# BSPD_V1_1.net
KiCad netlist of a schematic drawn in Altium Designer
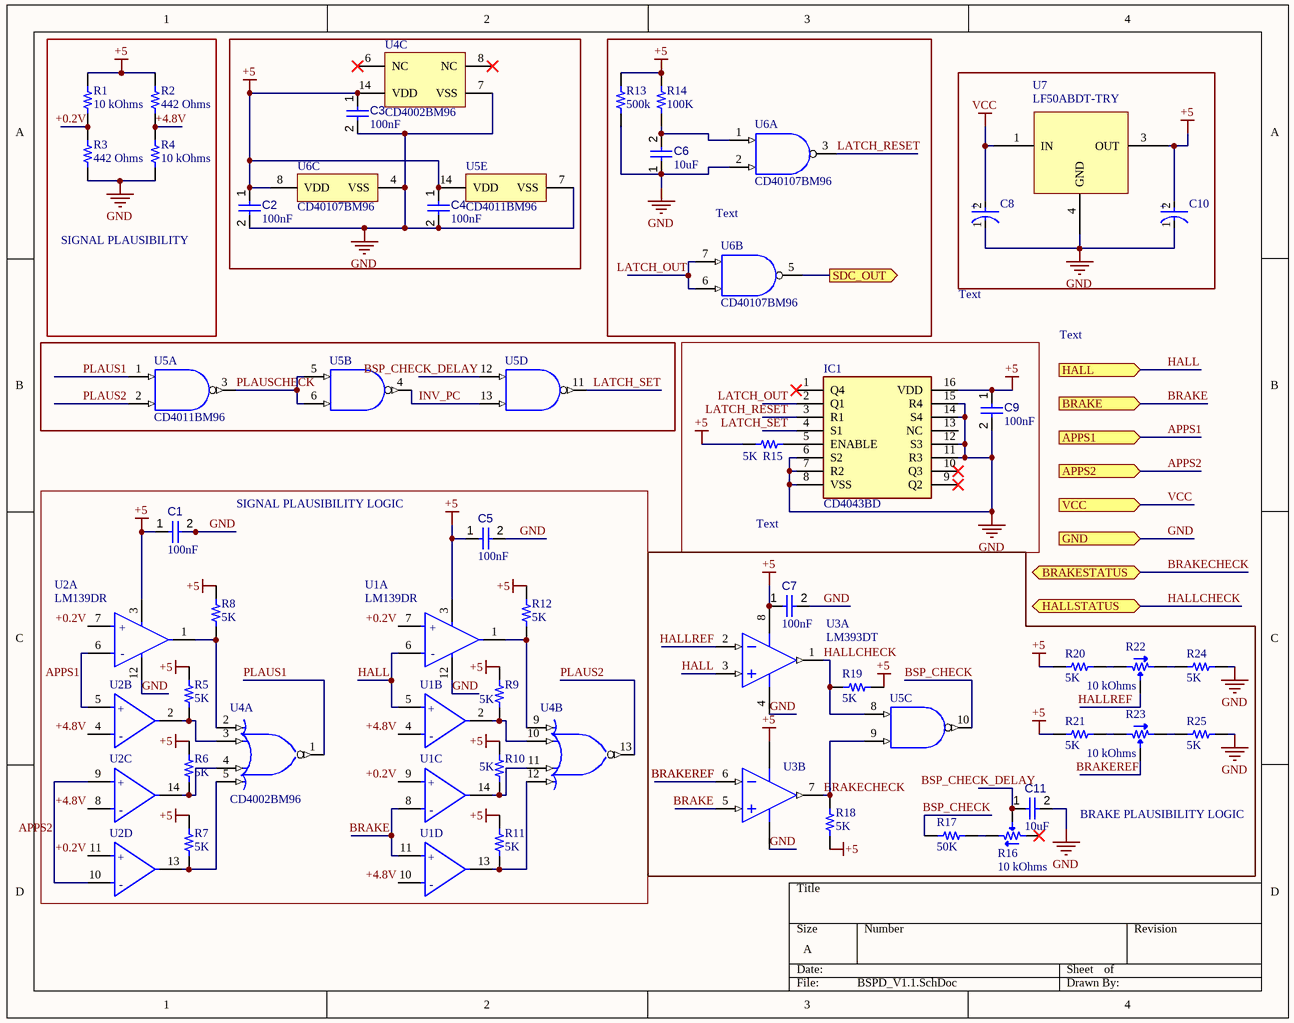
[diagram p0: BSPD_V1.1.SchDoc]

(export (version "E")
  (design (tool "Eeschema 10.0.6"))
  (components
    (comp (ref "C1")
      (value "100nF")
      (footprint "CAPC1608X90X40NL10T20")
      (description "Chip Capacitor, 100 nF, +/- 10%, 50 V, 0603 (1608 Metric)")
      (fields (field (name "TOLERANCE") "10%") (field (name "Comment") "Capacitor 100 nF +/-10% 50 V 0603"))
      (libsource (lib "Kennesaw Motorsports") (part "CAP-NP-2"))
    )
    (comp (ref "C2")
      (value "100nF")
      (footprint "CAPC1608X90X40NL10T20")
      (description "Chip Capacitor, 100 nF, +/- 10%, 50 V, 0603 (1608 Metric)")
      (fields (field (name "TOLERANCE") "10%") (field (name "Comment") "Capacitor 100 nF +/-10% 50 V 0603"))
      (libsource (lib "Kennesaw Motorsports") (part "CAP-NP-2"))
    )
    (comp (ref "C3")
      (value "100nF")
      (footprint "CAPC1608X90X40NL10T20")
      (description "Chip Capacitor, 100 nF, +/- 10%, 50 V, 0603 (1608 Metric)")
      (fields (field (name "TOLERANCE") "10%") (field (name "Comment") "Capacitor 100 nF +/-10% 50 V 0603"))
      (libsource (lib "Kennesaw Motorsports") (part "CAP-NP-2"))
    )
    (comp (ref "C4")
      (value "100nF")
      (footprint "CAPC1608X90X40NL10T20")
      (description "Chip Capacitor, 100 nF, +/- 10%, 50 V, 0603 (1608 Metric)")
      (fields (field (name "TOLERANCE") "10%") (field (name "Comment") "Capacitor 100 nF +/-10% 50 V 0603"))
      (libsource (lib "Kennesaw Motorsports") (part "CAP-NP-2"))
    )
    (comp (ref "C5")
      (value "100nF")
      (footprint "CAPC1608X90X40NL10T20")
      (description "Chip Capacitor, 100 nF, +/- 10%, 50 V, 0603 (1608 Metric)")
      (fields (field (name "TOLERANCE") "10%") (field (name "Comment") "Capacitor 100 nF +/-10% 50 V 0603"))
      (libsource (lib "Kennesaw Motorsports") (part "CAP-NP-2"))
    )
    (comp (ref "C6")
      (value "10uF")
      (footprint "CAPC1608X90X40NL10T20")
      (description "Chip Capacitor, 100 nF, +/- 10%, 50 V, 0603 (1608 Metric)")
      (fields (field (name "TOLERANCE") "10%") (field (name "Comment") "Capacitor 100 nF +/-10% 50 V 0603"))
      (libsource (lib "Kennesaw Motorsports") (part "CAP-NP-2"))
    )
    (comp (ref "C7")
      (value "100nF")
      (footprint "CAPC1608X90X40NL10T20")
      (description "Chip Capacitor, 100 nF, +/- 10%, 50 V, 0603 (1608 Metric)")
      (fields (field (name "TOLERANCE") "10%") (field (name "Comment") "Capacitor 100 nF +/-10% 50 V 0603"))
      (libsource (lib "Kennesaw Motorsports") (part "CAP-NP-2"))
    )
    (comp (ref "C8")
      (value "EEEFK1E100R")
      (footprint "FP-FKB-MFG")
      (description "CAP ALUM 10UF 20% 25V SMD")
      (fields (field (name "VOLTAGE") "25V") (field (name "TOLERANCE") "20%"))
      (libsource (lib "Altium Content Vault") (part "203bc49f2ac43e59fd269a8c329ed05"))
    )
    (comp (ref "C9")
      (value "100nF")
      (footprint "CAPC1608X90X40NL10T20")
      (description "Chip Capacitor, 100 nF, +/- 10%, 50 V, 0603 (1608 Metric)")
      (fields (field (name "TOLERANCE") "10%") (field (name "Comment") "Capacitor 100 nF +/-10% 50 V 0603"))
      (libsource (lib "Kennesaw Motorsports") (part "CAP-NP-2"))
    )
    (comp (ref "C10")
      (value "EEEFK1E100R")
      (footprint "FP-FKB-MFG")
      (description "CAP ALUM 10UF 20% 25V SMD")
      (fields (field (name "VOLTAGE") "25V") (field (name "TOLERANCE") "20%"))
      (libsource (lib "Altium Content Vault") (part "203bc49f2ac43e59fd269a8c329ed05"))
    )
    (comp (ref "C11")
      (value "10uF")
      (footprint "CAPC1608X90X40NL10T20")
      (description "Chip Capacitor, 100 nF, +/- 10%, 50 V, 0603 (1608 Metric)")
      (fields (field (name "TOLERANCE") "10%") (field (name "Comment") "Capacitor 100 nF +/-10% 50 V 0603"))
      (libsource (lib "Kennesaw Motorsports") (part "CAP-NP-2"))
    )
    (comp (ref "IC1")
      (value "CD4043BD")
      (footprint "SamacSys:SOIC127P600X175-16N")
      (description "Integrated Circuit")
      (fields (field (name "MOUSER PART NUMBER") "595-CD4043BD"))
      (libsource (lib "*") (part "CD4043BD"))
    )
    (comp (ref "R1")
      (value "10 kOhms")
      (footprint "RES 0603_1608")
      (description "RES SMD 10K OHM 0.1% 1/16W 0603")
      (fields
        (field (name "PART NUMBER") "CPF0603B10KE")
        (field (name "MANUFACTURER") "TE Connectivity Passive Product")
      )
      (libsource (lib "Celestial Altium Library - altium_library") (part "Resistor"))
    )
    (comp (ref "R2")
      (value "442 Ohms")
      (footprint "RES 0603_1608")
      (description "RES 442 OHM 1% 1/8W 0603")
      (fields
        (field (name "PART NUMBER") "RK73H1JTTD4420F")
        (field (name "MANUFACTURER") "KOA Speer Electronics, Inc.")
      )
      (libsource (lib "Celestial Altium Library - altium_library") (part "Resistor"))
    )
    (comp (ref "R3")
      (value "442 Ohms")
      (footprint "RES 0603_1608")
      (description "RES 442 OHM 1% 1/8W 0603")
      (fields
        (field (name "PART NUMBER") "RK73H1JTTD4420F")
        (field (name "MANUFACTURER") "KOA Speer Electronics, Inc.")
      )
      (libsource (lib "Celestial Altium Library - altium_library") (part "Resistor"))
    )
    (comp (ref "R4")
      (value "10 kOhms")
      (footprint "RES 0603_1608")
      (description "RES SMD 10K OHM 0.1% 1/16W 0603")
      (fields
        (field (name "PART NUMBER") "CPF0603B10KE")
        (field (name "MANUFACTURER") "TE Connectivity Passive Product")
      )
      (libsource (lib "Celestial Altium Library - altium_library") (part "Resistor"))
    )
    (comp (ref "R5")
      (value "5K")
      (footprint "RES 0603_1608")
      (description "CRGP 0603 5K6 1%")
      (fields
        (field (name "PART NUMBER") "CRGP0603F5K6")
        (field (name "MANUFACTURER") "TE Connectivity Passive Product")
      )
      (libsource (lib "Celestial Altium Library - altium_library") (part "Resistor"))
    )
    (comp (ref "R6")
      (value "5K")
      (footprint "RES 0603_1608")
      (description "CRGP 0603 5K6 1%")
      (fields
        (field (name "PART NUMBER") "CRGP0603F5K6")
        (field (name "MANUFACTURER") "TE Connectivity Passive Product")
      )
      (libsource (lib "Celestial Altium Library - altium_library") (part "Resistor"))
    )
    (comp (ref "R7")
      (value "5K")
      (footprint "RES 0603_1608")
      (description "CRGP 0603 5K6 1%")
      (fields
        (field (name "PART NUMBER") "CRGP0603F5K6")
        (field (name "MANUFACTURER") "TE Connectivity Passive Product")
      )
      (libsource (lib "Celestial Altium Library - altium_library") (part "Resistor"))
    )
    (comp (ref "R8")
      (value "5K")
      (footprint "RES 0603_1608")
      (description "CRGP 0603 5K6 1%")
      (fields
        (field (name "PART NUMBER") "CRGP0603F5K6")
        (field (name "MANUFACTURER") "TE Connectivity Passive Product")
      )
      (libsource (lib "Celestial Altium Library - altium_library") (part "Resistor"))
    )
    (comp (ref "R9")
      (value "5K")
      (footprint "RES 0603_1608")
      (description "CRGP 0603 5K6 1%")
      (fields
        (field (name "PART NUMBER") "CRGP0603F5K6")
        (field (name "MANUFACTURER") "TE Connectivity Passive Product")
      )
      (libsource (lib "Celestial Altium Library - altium_library") (part "Resistor"))
    )
    (comp (ref "R10")
      (value "5K")
      (footprint "RES 0603_1608")
      (description "CRGP 0603 5K6 1%")
      (fields
        (field (name "PART NUMBER") "CRGP0603F5K6")
        (field (name "MANUFACTURER") "TE Connectivity Passive Product")
      )
      (libsource (lib "Celestial Altium Library - altium_library") (part "Resistor"))
    )
    (comp (ref "R11")
      (value "5K")
      (footprint "RES 0603_1608")
      (description "CRGP 0603 5K6 1%")
      (fields
        (field (name "PART NUMBER") "CRGP0603F5K6")
        (field (name "MANUFACTURER") "TE Connectivity Passive Product")
      )
      (libsource (lib "Celestial Altium Library - altium_library") (part "Resistor"))
    )
    (comp (ref "R12")
      (value "5K")
      (footprint "RES 0603_1608")
      (description "CRGP 0603 5K6 1%")
      (fields
        (field (name "PART NUMBER") "CRGP0603F5K6")
        (field (name "MANUFACTURER") "TE Connectivity Passive Product")
      )
      (libsource (lib "Celestial Altium Library - altium_library") (part "Resistor"))
    )
    (comp (ref "R13")
      (value "500k")
      (footprint "RES 0603_1608")
      (description "CRGP 0603 5K6 1%")
      (fields
        (field (name "PART NUMBER") "CRGP0603F5K6")
        (field (name "MANUFACTURER") "TE Connectivity Passive Product")
      )
      (libsource (lib "Celestial Altium Library - altium_library") (part "Resistor"))
    )
    (comp (ref "R14")
      (value "100K")
      (footprint "RES 0603_1608")
      (description "CRGP 0603 5K6 1%")
      (fields
        (field (name "PART NUMBER") "CRGP0603F5K6")
        (field (name "MANUFACTURER") "TE Connectivity Passive Product")
      )
      (libsource (lib "Celestial Altium Library - altium_library") (part "Resistor"))
    )
    (comp (ref "R15")
      (value "5K")
      (footprint "RES 0603_1608")
      (description "CRGP 0603 5K6 1%")
      (fields
        (field (name "PART NUMBER") "CRGP0603F5K6")
        (field (name "MANUFACTURER") "TE Connectivity Passive Product")
      )
      (libsource (lib "Celestial Altium Library - altium_library") (part "Resistor"))
    )
    (comp (ref "R16")
      (value "10 kOhms")
      (footprint "POT BOURNS TRIMPOT TC33")
      (description "TRIMMER 10K OHM 0.1W J LEAD TOP")
      (fields (field (name "PART NUMBER") "TC33X-2-103E") (field (name "MANUFACTURER") "Bourns Inc."))
      (libsource (lib "Celestial Altium Library - altium_library") (part "Potentiometer"))
    )
    (comp (ref "R17")
      (value "50K")
      (footprint "RES 0603_1608")
      (description "CRGP 0603 5K6 1%")
      (fields
        (field (name "PART NUMBER") "CRGP0603F5K6")
        (field (name "MANUFACTURER") "TE Connectivity Passive Product")
      )
      (libsource (lib "Celestial Altium Library - altium_library") (part "Resistor"))
    )
    (comp (ref "R18")
      (value "5K")
      (footprint "RES 0603_1608")
      (description "CRGP 0603 5K6 1%")
      (fields
        (field (name "PART NUMBER") "CRGP0603F5K6")
        (field (name "MANUFACTURER") "TE Connectivity Passive Product")
      )
      (libsource (lib "Celestial Altium Library - altium_library") (part "Resistor"))
    )
    (comp (ref "R19")
      (value "5K")
      (footprint "RES 0603_1608")
      (description "CRGP 0603 5K6 1%")
      (fields
        (field (name "PART NUMBER") "CRGP0603F5K6")
        (field (name "MANUFACTURER") "TE Connectivity Passive Product")
      )
      (libsource (lib "Celestial Altium Library - altium_library") (part "Resistor"))
    )
    (comp (ref "R20")
      (value "5K")
      (footprint "RES 0603_1608")
      (description "CRGP 0603 5K6 1%")
      (fields
        (field (name "PART NUMBER") "CRGP0603F5K6")
        (field (name "MANUFACTURER") "TE Connectivity Passive Product")
      )
      (libsource (lib "Celestial Altium Library - altium_library") (part "Resistor"))
    )
    (comp (ref "R21")
      (value "5K")
      (footprint "RES 0603_1608")
      (description "CRGP 0603 5K6 1%")
      (fields
        (field (name "PART NUMBER") "CRGP0603F5K6")
        (field (name "MANUFACTURER") "TE Connectivity Passive Product")
      )
      (libsource (lib "Celestial Altium Library - altium_library") (part "Resistor"))
    )
    (comp (ref "R22")
      (value "10 kOhms")
      (footprint "POT BOURNS TRIMPOT TC33")
      (description "TRIMMER 10K OHM 0.1W J LEAD TOP")
      (fields (field (name "PART NUMBER") "TC33X-2-103E") (field (name "MANUFACTURER") "Bourns Inc."))
      (libsource (lib "Celestial Altium Library - altium_library") (part "Potentiometer"))
    )
    (comp (ref "R23")
      (value "10 kOhms")
      (footprint "POT BOURNS TRIMPOT TC33")
      (description "TRIMMER 10K OHM 0.1W J LEAD TOP")
      (fields (field (name "PART NUMBER") "TC33X-2-103E") (field (name "MANUFACTURER") "Bourns Inc."))
      (libsource (lib "Celestial Altium Library - altium_library") (part "Potentiometer"))
    )
    (comp (ref "R24")
      (value "5K")
      (footprint "RES 0603_1608")
      (description "CRGP 0603 5K6 1%")
      (fields
        (field (name "PART NUMBER") "CRGP0603F5K6")
        (field (name "MANUFACTURER") "TE Connectivity Passive Product")
      )
      (libsource (lib "Celestial Altium Library - altium_library") (part "Resistor"))
    )
    (comp (ref "R25")
      (value "5K")
      (footprint "RES 0603_1608")
      (description "CRGP 0603 5K6 1%")
      (fields
        (field (name "PART NUMBER") "CRGP0603F5K6")
        (field (name "MANUFACTURER") "TE Connectivity Passive Product")
      )
      (libsource (lib "Celestial Altium Library - altium_library") (part "Resistor"))
    )
    (comp (ref "U1")
      (value "LM139DR")
      (footprint "FP-D0014A-IPC_C")
      (description "IC QUAD DIFF COMPARATOR 14-SOIC")
      (libsource (lib "Altium Content Vault") (part "194f83ff06066585c623a61d885a339"))
    )
    (comp (ref "U2")
      (value "LM139DR")
      (footprint "FP-D0014A-IPC_C")
      (description "IC QUAD DIFF COMPARATOR 14-SOIC")
      (libsource (lib "Altium Content Vault") (part "194f83ff06066585c623a61d885a339"))
    )
    (comp (ref "U3")
      (value "LM393DT")
      (footprint "STM-SO-8_D_L")
      (description "Low-Power, Dual-Voltage Comparator, 2 to 36 V, 0 to 70 degC, 8-Pin SOIC (SO), RoHS, Tape and Reel")
      (fields (field (name "MANUFACTURER") "STMicroelectronics"))
      (libsource (lib "Altium Content Vault") (part "STM-LM393-SO8"))
    )
    (comp (ref "U4")
      (value "CD4002BM96")
      (footprint "D0014A_L")
      (description "CMOS Dual 4-Input NOR Gate, D0014A, LARGE T&R")
      (fields
        (field (name "MANUFACTURER") "Texas Instruments")
        (field (name "GENERIC PART NUMBER") "CD4002B")
      )
      (libsource (lib "Altium Content Vault") (part "TI-CD4002B-D0014A-14"))
    )
    (comp (ref "U5")
      (value "CD4011BM96")
      (footprint "D0014A_L")
      (description "CMOS Quad 2-Input NAND Gate, D0014A, LARGE T&R")
      (fields
        (field (name "MANUFACTURER") "Texas Instruments")
        (field (name "GENERIC PART NUMBER") "CD4011B")
      )
      (libsource (lib "Altium Content Vault") (part "TI-NAND-4-2IN-14_A"))
    )
    (comp (ref "U6")
      (value "CD40107BM96")
      (footprint "D0008A_N")
      (description "CMOS Dual 2-Input NAND Buffer/Driver, D0008A, LARGE T&R")
      (fields
        (field (name "MANUFACTURER") "Texas Instruments")
        (field (name "GENERIC PART NUMBER") "CD40107B")
      )
      (libsource (lib "Altium Content Vault") (part "TI-CD40107B-8"))
    )
    (comp (ref "U7")
      (value "LF50ABDT-TRY")
      (footprint "DPAK228P972X238-3N")
      (description "Linear Voltage Regulator IC Positive Fixed 1 Output 500mA DPAK")
      (libsource (lib "LF50ABDT-TRY") (part "LF50ABDT-TRY"))
    )
  )
  (nets
    (net (code "1") (name "+5") (class "Default")
      (node (ref "C1") (pin "1") (pinfunction "1_1") (pintype "passive"))
      (node (ref "C10") (pin "2") (pinfunction "A_2") (pintype "passive"))
      (node (ref "C2") (pin "1") (pinfunction "1_1") (pintype "passive"))
      (node (ref "C3") (pin "1") (pinfunction "1_1") (pintype "passive"))
      (node (ref "C4") (pin "1") (pinfunction "1_1") (pintype "passive"))
      (node (ref "C5") (pin "1") (pinfunction "1_1") (pintype "passive"))
      (node (ref "C7") (pin "1") (pinfunction "1_1") (pintype "passive"))
      (node (ref "C9") (pin "1") (pinfunction "1_1") (pintype "passive"))
      (node (ref "IC1") (pin "16") (pinfunction "VDD_16") (pintype "passive"))
      (node (ref "R1") (pin "2") (pinfunction "2_2") (pintype "passive"))
      (node (ref "R10") (pin "1") (pinfunction "1_1") (pintype "passive"))
      (node (ref "R11") (pin "1") (pinfunction "1_1") (pintype "passive"))
      (node (ref "R12") (pin "1") (pinfunction "1_1") (pintype "passive"))
      (node (ref "R13") (pin "2") (pinfunction "2_2") (pintype "passive"))
      (node (ref "R14") (pin "2") (pinfunction "2_2") (pintype "passive"))
      (node (ref "R15") (pin "2") (pinfunction "2_2") (pintype "passive"))
      (node (ref "R18") (pin "1") (pinfunction "1_1") (pintype "passive"))
      (node (ref "R19") (pin "1") (pinfunction "1_1") (pintype "passive"))
      (node (ref "R2") (pin "1") (pinfunction "1_1") (pintype "passive"))
      (node (ref "R20") (pin "1") (pinfunction "1_1") (pintype "passive"))
      (node (ref "R21") (pin "1") (pinfunction "1_1") (pintype "passive"))
      (node (ref "R5") (pin "1") (pinfunction "1_1") (pintype "passive"))
      (node (ref "R6") (pin "1") (pinfunction "1_1") (pintype "passive"))
      (node (ref "R7") (pin "1") (pinfunction "1_1") (pintype "passive"))
      (node (ref "R8") (pin "1") (pinfunction "1_1") (pintype "passive"))
      (node (ref "R9") (pin "1") (pinfunction "1_1") (pintype "passive"))
      (node (ref "U1") (pin "3") (pinfunction "VCC_3") (pintype "power_in"))
      (node (ref "U2") (pin "3") (pinfunction "VCC_3") (pintype "power_in"))
      (node (ref "U3") (pin "8") (pinfunction "VCC+_8") (pintype "power_in"))
      (node (ref "U4") (pin "14") (pinfunction "VDD_14") (pintype "power_in"))
      (node (ref "U5") (pin "14") (pinfunction "VDD_14") (pintype "power_in"))
      (node (ref "U6") (pin "8") (pinfunction "VDD_8") (pintype "power_in"))
      (node (ref "U7") (pin "3") (pinfunction "OUT_3") (pintype "power_in"))
    )
    (net (code "2") (name "/+0.2V") (class "Default")
      (node (ref "R1") (pin "1") (pinfunction "1_1") (pintype "passive"))
      (node (ref "R3") (pin "2") (pinfunction "2_2") (pintype "passive"))
      (node (ref "U1") (pin "7") (pinfunction "1IN+_7") (pintype "tri_state"))
      (node (ref "U1") (pin "9") (pinfunction "3IN+_9") (pintype "tri_state"))
      (node (ref "U2") (pin "11") (pinfunction "4IN+_11") (pintype "tri_state"))
      (node (ref "U2") (pin "7") (pinfunction "1IN+_7") (pintype "tri_state"))
    )
    (net (code "3") (name "/+4.8V") (class "Default")
      (node (ref "R2") (pin "2") (pinfunction "2_2") (pintype "passive"))
      (node (ref "R4") (pin "2") (pinfunction "2_2") (pintype "passive"))
      (node (ref "U1") (pin "10") (pinfunction "4IN-_10") (pintype "tri_state"))
      (node (ref "U1") (pin "4") (pinfunction "2IN-_4") (pintype "tri_state"))
      (node (ref "U2") (pin "4") (pinfunction "2IN-_4") (pintype "tri_state"))
      (node (ref "U2") (pin "8") (pinfunction "3IN-_8") (pintype "tri_state"))
    )
    (net (code "4") (name "/APPS1") (class "Default")
      (node (ref "U2") (pin "5") (pinfunction "2IN+_5") (pintype "tri_state"))
      (node (ref "U2") (pin "6") (pinfunction "1IN-_6") (pintype "tri_state"))
    )
    (net (code "5") (name "/APPS2") (class "Default")
      (node (ref "U2") (pin "10") (pinfunction "4IN-_10") (pintype "tri_state"))
      (node (ref "U2") (pin "9") (pinfunction "3IN+_9") (pintype "tri_state"))
    )
    (net (code "6") (name "/BRAKE") (class "Default")
      (node (ref "U1") (pin "11") (pinfunction "4IN+_11") (pintype "tri_state"))
      (node (ref "U1") (pin "8") (pinfunction "3IN-_8") (pintype "tri_state"))
      (node (ref "U3") (pin "5") (pinfunction "IN2+_5") (pintype "input"))
    )
    (net (code "7") (name "/BRAKECHECK") (class "Default")
      (node (ref "R18") (pin "2") (pinfunction "2_2") (pintype "passive"))
      (node (ref "U3") (pin "7") (pinfunction "OUT2_7") (pintype "output"))
      (node (ref "U5") (pin "9") (pinfunction "F_9") (pintype "input"))
    )
    (net (code "8") (name "/BRAKEREF") (class "Default")
      (node (ref "R23") (pin "2") (pinfunction "2_2") (pintype "passive"))
      (node (ref "U3") (pin "6") (pinfunction "IN2-_6") (pintype "input"))
    )
    (net (code "9") (name "/BSP_CHECK") (class "Default")
      (node (ref "R17") (pin "2") (pinfunction "2_2") (pintype "passive"))
      (node (ref "U5") (pin "10") (pinfunction "L_10") (pintype "output"))
    )
    (net (code "10") (name "/BSP_CHECK_DELAY") (class "Default")
      (node (ref "C11") (pin "1") (pinfunction "1_1") (pintype "passive"))
      (node (ref "R16") (pin "2") (pinfunction "2_2") (pintype "passive"))
      (node (ref "U5") (pin "12") (pinfunction "G_12") (pintype "input"))
    )
    (net (code "11") (name "/HALL") (class "Default")
      (node (ref "U1") (pin "5") (pinfunction "2IN+_5") (pintype "tri_state"))
      (node (ref "U1") (pin "6") (pinfunction "1IN-_6") (pintype "tri_state"))
      (node (ref "U3") (pin "3") (pinfunction "IN1+_3") (pintype "input"))
    )
    (net (code "12") (name "/HALLCHECK") (class "Default")
      (node (ref "R19") (pin "2") (pinfunction "2_2") (pintype "passive"))
      (node (ref "U3") (pin "1") (pinfunction "OUT1_1") (pintype "output"))
      (node (ref "U5") (pin "8") (pinfunction "E_8") (pintype "input"))
    )
    (net (code "13") (name "/HALLREF") (class "Default")
      (node (ref "R22") (pin "2") (pinfunction "2_2") (pintype "passive"))
      (node (ref "U3") (pin "2") (pinfunction "IN1-_2") (pintype "input"))
    )
    (net (code "14") (name "/INV_PC") (class "Default")
      (node (ref "U5") (pin "13") (pinfunction "H_13") (pintype "input"))
      (node (ref "U5") (pin "4") (pinfunction "K_4") (pintype "output"))
    )
    (net (code "15") (name "/LATCH_OUT") (class "Default")
      (node (ref "IC1") (pin "2") (pinfunction "Q1_2") (pintype "passive"))
      (node (ref "U6") (pin "6") (pinfunction "E_6") (pintype "input"))
      (node (ref "U6") (pin "7") (pinfunction "D_7") (pintype "input"))
    )
    (net (code "16") (name "/LATCH_RESET") (class "Default")
      (node (ref "IC1") (pin "3") (pinfunction "R1_3") (pintype "passive"))
      (node (ref "U6") (pin "3") (pinfunction "C_3") (pintype "open_collector"))
    )
    (net (code "17") (name "/LATCH_SET") (class "Default")
      (node (ref "IC1") (pin "4") (pinfunction "S1_4") (pintype "passive"))
      (node (ref "U5") (pin "11") (pinfunction "M_11") (pintype "output"))
    )
    (net (code "18") (name "/PLAUS1") (class "Default")
      (node (ref "U4") (pin "1") (pinfunction "J_1") (pintype "output"))
      (node (ref "U5") (pin "1") (pinfunction "A_1") (pintype "input"))
    )
    (net (code "19") (name "/PLAUS2") (class "Default")
      (node (ref "U4") (pin "13") (pinfunction "K_13") (pintype "output"))
      (node (ref "U5") (pin "2") (pinfunction "B_2") (pintype "input"))
    )
    (net (code "20") (name "/PLAUSCHECK") (class "Default")
      (node (ref "U5") (pin "3") (pinfunction "J_3") (pintype "output"))
      (node (ref "U5") (pin "5") (pinfunction "C_5") (pintype "input"))
      (node (ref "U5") (pin "6") (pinfunction "D_6") (pintype "input"))
    )
    (net (code "21") (name "/SDC_OUT") (class "Default")
      (node (ref "U6") (pin "5") (pinfunction "F_5") (pintype "open_collector"))
    )
    (net (code "22") (name "GND") (class "Default")
      (node (ref "C1") (pin "2") (pinfunction "2_2") (pintype "passive"))
      (node (ref "C10") (pin "1") (pinfunction "C_1") (pintype "passive"))
      (node (ref "C11") (pin "2") (pinfunction "2_2") (pintype "passive"))
      (node (ref "C2") (pin "2") (pinfunction "2_2") (pintype "passive"))
      (node (ref "C3") (pin "2") (pinfunction "2_2") (pintype "passive"))
      (node (ref "C4") (pin "2") (pinfunction "2_2") (pintype "passive"))
      (node (ref "C5") (pin "2") (pinfunction "2_2") (pintype "passive"))
      (node (ref "C6") (pin "1") (pinfunction "1_1") (pintype "passive"))
      (node (ref "C7") (pin "2") (pinfunction "2_2") (pintype "passive"))
      (node (ref "C8") (pin "1") (pinfunction "C_1") (pintype "passive"))
      (node (ref "C9") (pin "2") (pinfunction "2_2") (pintype "passive"))
      (node (ref "IC1") (pin "11") (pinfunction "R3_11") (pintype "passive"))
      (node (ref "IC1") (pin "12") (pinfunction "S3_12") (pintype "passive"))
      (node (ref "IC1") (pin "14") (pinfunction "S4_14") (pintype "passive"))
      (node (ref "IC1") (pin "15") (pinfunction "R4_15") (pintype "passive"))
      (node (ref "IC1") (pin "6") (pinfunction "S2_6") (pintype "passive"))
      (node (ref "IC1") (pin "7") (pinfunction "R2_7") (pintype "passive"))
      (node (ref "IC1") (pin "8") (pinfunction "VSS_8") (pintype "passive"))
      (node (ref "R13") (pin "1") (pinfunction "1_1") (pintype "passive"))
      (node (ref "R24") (pin "1") (pinfunction "1_1") (pintype "passive"))
      (node (ref "R25") (pin "1") (pinfunction "1_1") (pintype "passive"))
      (node (ref "R3") (pin "1") (pinfunction "1_1") (pintype "passive"))
      (node (ref "R4") (pin "1") (pinfunction "1_1") (pintype "passive"))
      (node (ref "U1") (pin "12") (pinfunction "GND_12") (pintype "power_in"))
      (node (ref "U2") (pin "12") (pinfunction "GND_12") (pintype "power_in"))
      (node (ref "U3") (pin "4") (pinfunction "VCC-_4") (pintype "power_in"))
      (node (ref "U4") (pin "7") (pinfunction "VSS_7") (pintype "power_in"))
      (node (ref "U5") (pin "7") (pinfunction "VSS_7") (pintype "power_in"))
      (node (ref "U6") (pin "2") (pinfunction "B_2") (pintype "input"))
      (node (ref "U6") (pin "4") (pinfunction "VSS_4") (pintype "power_in"))
      (node (ref "U7") (pin "4") (pinfunction "GND_4") (pintype "power_in"))
    )
    (net (code "23") (name "Net-(IC1-ENABLE)") (class "Default")
      (node (ref "IC1") (pin "5") (pinfunction "ENABLE_5") (pintype "passive"))
      (node (ref "R15") (pin "1") (pinfunction "1_1") (pintype "passive"))
    )
    (net (code "24") (name "Net-(R16-Pad3)") (class "Default")
      (node (ref "R16") (pin "3") (pinfunction "3_3") (pintype "passive"))
      (node (ref "R17") (pin "1") (pinfunction "1_1") (pintype "passive"))
    )
    (net (code "25") (name "Net-(R20-Pad2)") (class "Default")
      (node (ref "R20") (pin "2") (pinfunction "2_2") (pintype "passive"))
      (node (ref "R22") (pin "1") (pinfunction "1_1") (pintype "passive"))
    )
    (net (code "26") (name "Net-(R21-Pad2)") (class "Default")
      (node (ref "R21") (pin "2") (pinfunction "2_2") (pintype "passive"))
      (node (ref "R23") (pin "1") (pinfunction "1_1") (pintype "passive"))
    )
    (net (code "27") (name "Net-(R22-Pad3)") (class "Default")
      (node (ref "R22") (pin "3") (pinfunction "3_3") (pintype "passive"))
      (node (ref "R24") (pin "2") (pinfunction "2_2") (pintype "passive"))
    )
    (net (code "28") (name "Net-(R23-Pad3)") (class "Default")
      (node (ref "R23") (pin "3") (pinfunction "3_3") (pintype "passive"))
      (node (ref "R25") (pin "2") (pinfunction "2_2") (pintype "passive"))
    )
    (net (code "29") (name "Net-(U1A-1OUT)") (class "Default")
      (node (ref "R12") (pin "2") (pinfunction "2_2") (pintype "passive"))
      (node (ref "U1") (pin "1") (pinfunction "1OUT_1") (pintype "passive"))
      (node (ref "U4") (pin "9") (pinfunction "E_9") (pintype "input"))
    )
    (net (code "30") (name "Net-(U1B-2OUT)") (class "Default")
      (node (ref "R9") (pin "2") (pinfunction "2_2") (pintype "passive"))
      (node (ref "U1") (pin "2") (pinfunction "2OUT_2") (pintype "passive"))
      (node (ref "U4") (pin "10") (pinfunction "F_10") (pintype "input"))
    )
    (net (code "31") (name "Net-(U1C-OUT3)") (class "Default")
      (node (ref "R10") (pin "2") (pinfunction "2_2") (pintype "passive"))
      (node (ref "U1") (pin "14") (pinfunction "OUT3_14") (pintype "passive"))
      (node (ref "U4") (pin "11") (pinfunction "G_11") (pintype "input"))
    )
    (net (code "32") (name "Net-(U1D-OUT4)") (class "Default")
      (node (ref "R11") (pin "2") (pinfunction "2_2") (pintype "passive"))
      (node (ref "U1") (pin "13") (pinfunction "OUT4_13") (pintype "passive"))
      (node (ref "U4") (pin "12") (pinfunction "H_12") (pintype "input"))
    )
    (net (code "33") (name "Net-(U2A-1OUT)") (class "Default")
      (node (ref "R8") (pin "2") (pinfunction "2_2") (pintype "passive"))
      (node (ref "U2") (pin "1") (pinfunction "1OUT_1") (pintype "passive"))
      (node (ref "U4") (pin "2") (pinfunction "A_2") (pintype "input"))
    )
    (net (code "34") (name "Net-(U2B-2OUT)") (class "Default")
      (node (ref "R5") (pin "2") (pinfunction "2_2") (pintype "passive"))
      (node (ref "U2") (pin "2") (pinfunction "2OUT_2") (pintype "passive"))
      (node (ref "U4") (pin "3") (pinfunction "B_3") (pintype "input"))
    )
    (net (code "35") (name "Net-(U2C-OUT3)") (class "Default")
      (node (ref "R6") (pin "2") (pinfunction "2_2") (pintype "passive"))
      (node (ref "U2") (pin "14") (pinfunction "OUT3_14") (pintype "passive"))
      (node (ref "U4") (pin "4") (pinfunction "C_4") (pintype "input"))
    )
    (net (code "36") (name "Net-(U2D-OUT4)") (class "Default")
      (node (ref "R7") (pin "2") (pinfunction "2_2") (pintype "passive"))
      (node (ref "U2") (pin "13") (pinfunction "OUT4_13") (pintype "passive"))
      (node (ref "U4") (pin "5") (pinfunction "D_5") (pintype "input"))
    )
    (net (code "37") (name "Net-(U6A-A)") (class "Default")
      (node (ref "C6") (pin "2") (pinfunction "2_2") (pintype "passive"))
      (node (ref "R14") (pin "1") (pinfunction "1_1") (pintype "passive"))
      (node (ref "U6") (pin "1") (pinfunction "A_1") (pintype "input"))
    )
    (net (code "38") (name "VCC") (class "Default")
      (node (ref "C8") (pin "2") (pinfunction "A_2") (pintype "passive"))
      (node (ref "U7") (pin "1") (pinfunction "IN_1") (pintype "power_in"))
    )
    (net (code "39") (name "unconnected-(IC1-NC-Pad13)") (class "Default")
      (node (ref "IC1") (pin "13") (pinfunction "NC_13") (pintype "passive"))
    )
    (net (code "40") (name "unconnected-(IC1-Q2-Pad9)") (class "Default")
      (node (ref "IC1") (pin "9") (pinfunction "Q2_9") (pintype "passive+no_connect"))
    )
    (net (code "41") (name "unconnected-(IC1-Q3-Pad10)") (class "Default")
      (node (ref "IC1") (pin "10") (pinfunction "Q3_10") (pintype "passive+no_connect"))
    )
    (net (code "42") (name "unconnected-(IC1-Q4-Pad1)") (class "Default")
      (node (ref "IC1") (pin "1") (pinfunction "Q4_1") (pintype "passive+no_connect"))
    )
    (net (code "43") (name "unconnected-(R16-Pad1)") (class "Default")
      (node (ref "R16") (pin "1") (pinfunction "1_1") (pintype "passive+no_connect"))
    )
    (net (code "44") (name "unconnected-(U4C-NC-Pad6)") (class "Default")
      (node (ref "U4") (pin "6") (pinfunction "NC_6") (pintype "passive+no_connect"))
    )
    (net (code "45") (name "unconnected-(U4C-NC-Pad8)") (class "Default")
      (node (ref "U4") (pin "8") (pinfunction "NC_8") (pintype "passive+no_connect"))
    )
  )
)
